# KeyCade.net
KiCad netlist of a schematic drawn in EAGLE
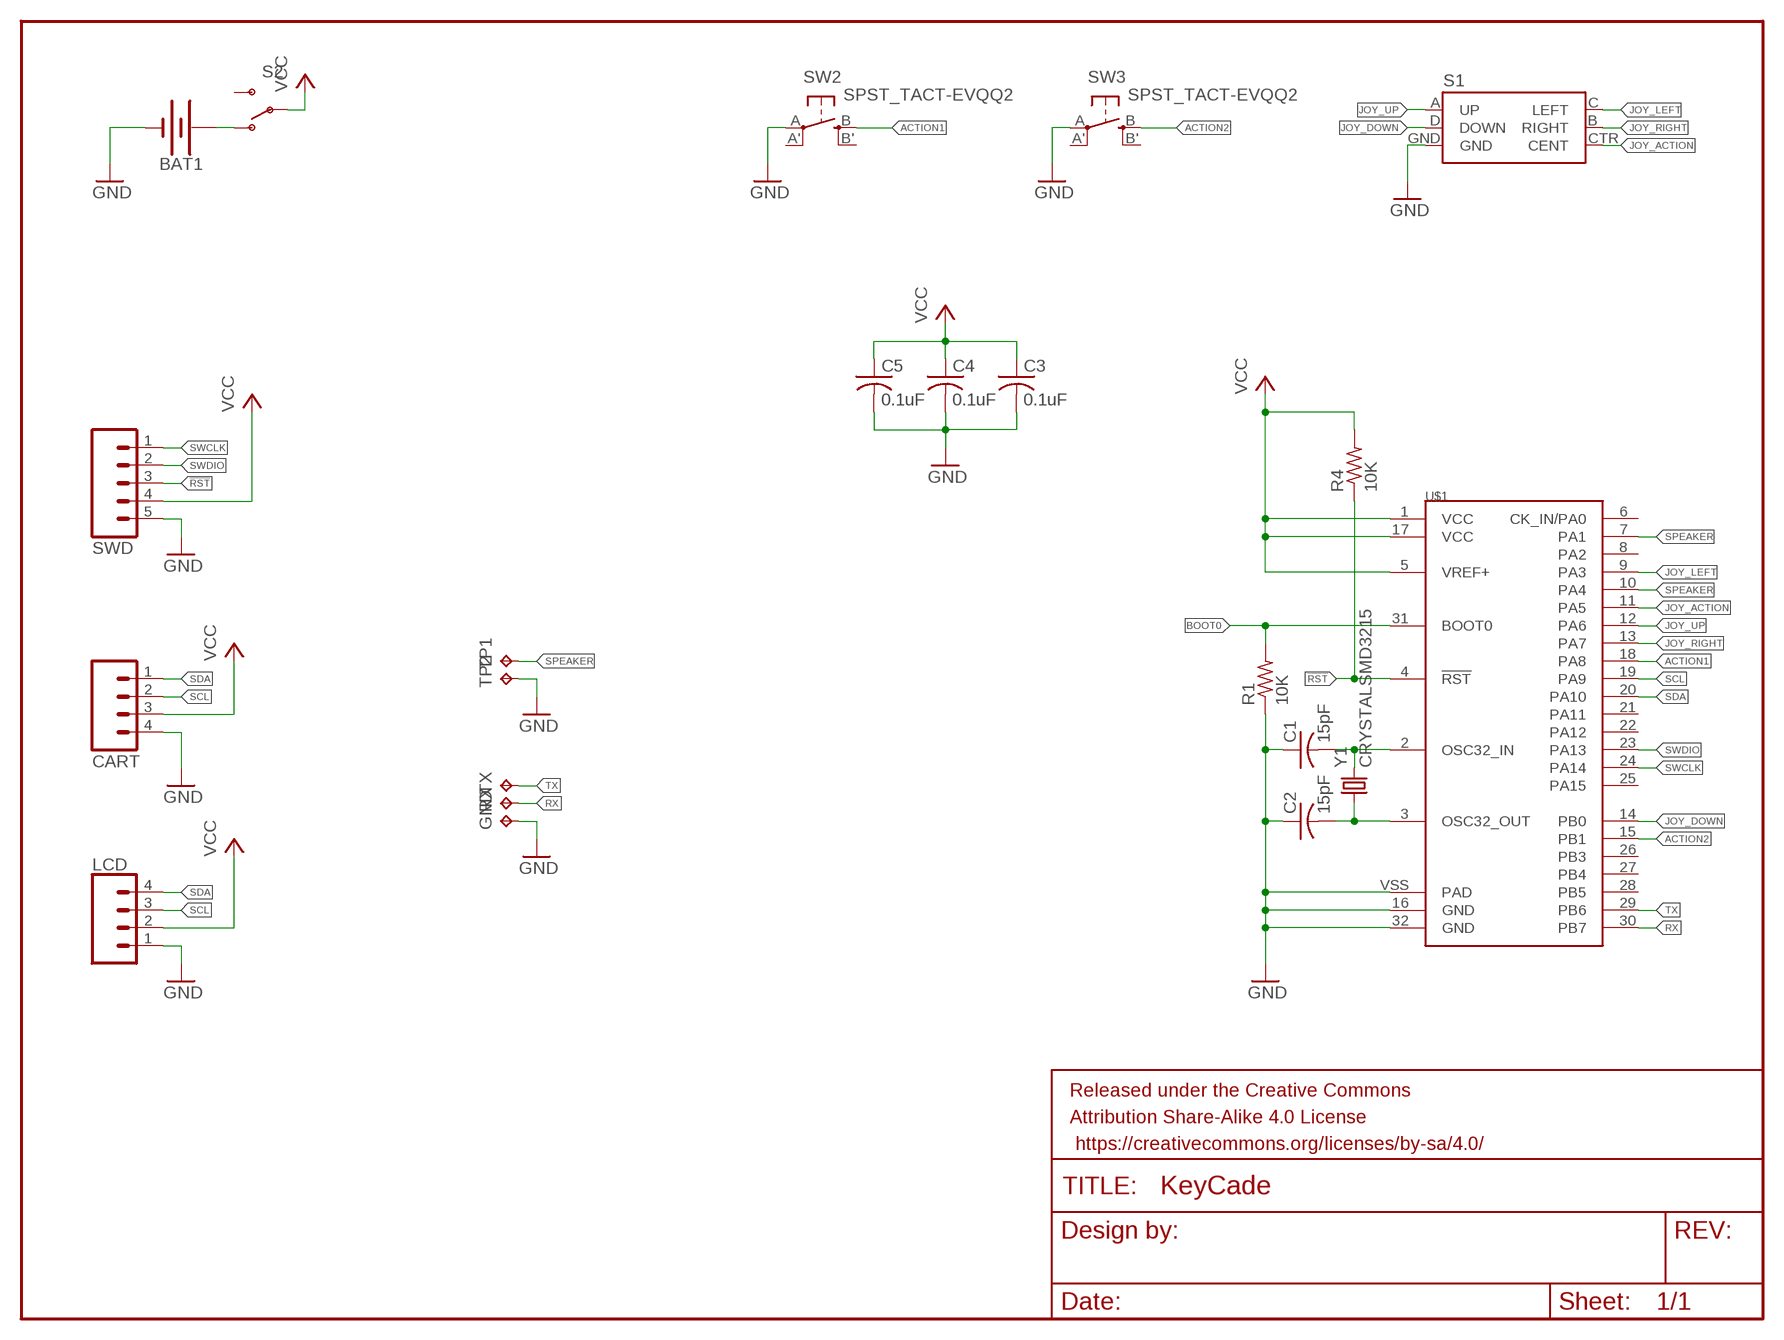
[diagram p0: schematic, sheet 1]

(export (version "E")
  (design (tool "Eeschema 10.0.6"))
  (components
    (comp (ref "BAT1")
      (value "BATTERY-20MM_SMD_4LEGS")
      (footprint "eagle-import:BATTCON_20MM_4LEGS")
      (libsource (lib "eagle-import") (part "BATTERY-20MM_SMD_4LEGS"))
    )
    (comp (ref "C1")
      (value "15pF")
      (footprint "eagle-import:C0603")
      (libsource (lib "eagle-import") (part "C-USC0603"))
    )
    (comp (ref "C2")
      (value "15pF")
      (footprint "eagle-import:C0603")
      (libsource (lib "eagle-import") (part "C-USC0603"))
    )
    (comp (ref "C3")
      (value "0.1uF")
      (footprint "eagle-import:C0603")
      (libsource (lib "eagle-import") (part "C-USC0603"))
    )
    (comp (ref "C4")
      (value "0.1uF")
      (footprint "eagle-import:C0603")
      (libsource (lib "eagle-import") (part "C-USC0603"))
    )
    (comp (ref "C5")
      (value "0.1uF")
      (footprint "eagle-import:C0603")
      (libsource (lib "eagle-import") (part "C-USC0603"))
    )
    (comp (ref "CART")
      (value "M04PTH")
      (footprint "eagle-import:1X04@1")
      (libsource (lib "eagle-import") (part "M04PTH"))
    )
    (comp (ref "FRAME1")
      (value "FRAME-LETTER")
      (footprint "eagle-import:CREATIVE_COMMONS")
      (libsource (lib "eagle-import") (part "FRAME-LETTER"))
    )
    (comp (ref "GND")
      (value "TPTP17SQ")
      (footprint "eagle-import:TP17SQ")
      (libsource (lib "eagle-import") (part "TPTP17SQ"))
    )
    (comp (ref "LCD")
      (value "CONN_04SMD_RA_FEMALE")
      (footprint "eagle-import:1X04_SMD_RA_FEMALE")
      (libsource (lib "eagle-import") (part "CONN_04SMD_RA_FEMALE"))
    )
    (comp (ref "R1")
      (value "10K")
      (footprint "eagle-import:R0603")
      (libsource (lib "eagle-import") (part "R-US_R0603"))
    )
    (comp (ref "R4")
      (value "10K")
      (footprint "eagle-import:R0603")
      (libsource (lib "eagle-import") (part "R-US_R0603"))
    )
    (comp (ref "RX")
      (value "TPTP17SQ")
      (footprint "eagle-import:TP17SQ")
      (libsource (lib "eagle-import") (part "TPTP17SQ"))
    )
    (comp (ref "S1")
      (value "JOYSTICK_MINI")
      (footprint "eagle-import:JOYSTICK_MINI")
      (libsource (lib "eagle-import") (part "JOYSTICK_MINI"))
    )
    (comp (ref "S2")
      (value "SWITCH-SPDT-SMD-A")
      (footprint "eagle-import:SWITCH-SPST-SMD-A")
      (libsource (lib "eagle-import") (part "SWITCH-SPDT-SMD-A"))
    )
    (comp (ref "SW2")
      (value "SPST_TACT-EVQQ2")
      (footprint "eagle-import:EVQ-Q2")
      (libsource (lib "eagle-import") (part "SPST_TACT-EVQQ2"))
    )
    (comp (ref "SW3")
      (value "SPST_TACT-EVQQ2")
      (footprint "eagle-import:EVQ-Q2")
      (libsource (lib "eagle-import") (part "SPST_TACT-EVQQ2"))
    )
    (comp (ref "SWD")
      (value "M05PTH")
      (footprint "eagle-import:1X05")
      (libsource (lib "eagle-import") (part "M05PTH"))
    )
    (comp (ref "TP1")
      (value "TPTP17SQ")
      (footprint "eagle-import:TP17SQ")
      (libsource (lib "eagle-import") (part "TPTP17SQ"))
    )
    (comp (ref "TP2")
      (value "TPTP17SQ")
      (footprint "eagle-import:TP17SQ")
      (libsource (lib "eagle-import") (part "TPTP17SQ"))
    )
    (comp (ref "TX")
      (value "TPTP17SQ")
      (footprint "eagle-import:TP17SQ")
      (libsource (lib "eagle-import") (part "TPTP17SQ"))
    )
    (comp (ref "U$1")
      (value "STM32L432KCIC")
      (footprint "eagle-import:UFQFPN32")
      (libsource (lib "eagle-import") (part "STM32L432KCIC"))
    )
    (comp (ref "Y1")
      (value "CRYSTALSMD3215")
      (footprint "eagle-import:ST3215SB_32X15")
      (libsource (lib "eagle-import") (part "CRYSTALSMD3215"))
    )
  )
  (nets
    (net (code "1") (name "/~{RST}") (class "Default")
      (node (ref "R4") (pin "1") (pinfunction "1_1") (pintype "passive"))
      (node (ref "SWD") (pin "3") (pinfunction "3_3") (pintype "passive"))
      (node (ref "U$1") (pin "4") (pinfunction "~{RST}_4") (pintype "bidirectional"))
    )
    (net (code "2") (name "ACTION1") (class "Default")
      (node (ref "SW2") (pin "B") (pinfunction "S_B") (pintype "passive"))
      (node (ref "U$1") (pin "18") (pinfunction "PA8_18") (pintype "bidirectional"))
    )
    (net (code "3") (name "ACTION2") (class "Default")
      (node (ref "SW3") (pin "B") (pinfunction "S_B") (pintype "passive"))
      (node (ref "U$1") (pin "15") (pinfunction "PB1_15") (pintype "bidirectional"))
    )
    (net (code "4") (name "BOOT0") (class "Default")
      (node (ref "R1") (pin "2") (pinfunction "2_2") (pintype "passive"))
      (node (ref "U$1") (pin "31") (pinfunction "BOOT0_31") (pintype "bidirectional"))
    )
    (net (code "5") (name "GND") (class "Default")
      (node (ref "BAT1") (pin "NEGATIVE") (pinfunction "-_NEGATIVE") (pintype "power_in"))
      (node (ref "C1") (pin "1") (pinfunction "1_1") (pintype "passive"))
      (node (ref "C2") (pin "1") (pinfunction "1_1") (pintype "passive"))
      (node (ref "C3") (pin "2") (pinfunction "2_2") (pintype "passive"))
      (node (ref "C4") (pin "2") (pinfunction "2_2") (pintype "passive"))
      (node (ref "C5") (pin "2") (pinfunction "2_2") (pintype "passive"))
      (node (ref "CART") (pin "4") (pinfunction "4_4") (pintype "passive"))
      (node (ref "GND") (pin "TP") (pinfunction "TP_TP") (pintype "input"))
      (node (ref "LCD") (pin "1") (pinfunction "1_1") (pintype "passive"))
      (node (ref "R1") (pin "1") (pinfunction "1_1") (pintype "passive"))
      (node (ref "S1") (pin "GND") (pinfunction "GND_GND") (pintype "bidirectional"))
      (node (ref "SW2") (pin "A") (pinfunction "P_A") (pintype "passive"))
      (node (ref "SW3") (pin "A") (pinfunction "P_A") (pintype "passive"))
      (node (ref "SWD") (pin "5") (pinfunction "5_5") (pintype "passive"))
      (node (ref "TP2") (pin "TP") (pinfunction "TP_TP") (pintype "input"))
      (node (ref "U$1") (pin "16") (pinfunction "GND_16") (pintype "bidirectional"))
      (node (ref "U$1") (pin "32") (pinfunction "GND_32") (pintype "bidirectional"))
      (node (ref "U$1") (pin "VSS") (pinfunction "PAD_VSS") (pintype "bidirectional"))
    )
    (net (code "6") (name "JOY_ACTION") (class "Default")
      (node (ref "S1") (pin "CTR") (pinfunction "CENT_CTR") (pintype "bidirectional"))
      (node (ref "U$1") (pin "11") (pinfunction "PA5_11") (pintype "bidirectional"))
    )
    (net (code "7") (name "JOY_DOWN") (class "Default")
      (node (ref "S1") (pin "D") (pinfunction "DOWN_D") (pintype "bidirectional"))
      (node (ref "U$1") (pin "14") (pinfunction "PB0_14") (pintype "bidirectional"))
    )
    (net (code "8") (name "JOY_LEFT") (class "Default")
      (node (ref "S1") (pin "C") (pinfunction "LEFT_C") (pintype "bidirectional"))
      (node (ref "U$1") (pin "9") (pinfunction "PA3_9") (pintype "bidirectional"))
    )
    (net (code "9") (name "JOY_RIGHT") (class "Default")
      (node (ref "S1") (pin "B") (pinfunction "RIGHT_B") (pintype "bidirectional"))
      (node (ref "U$1") (pin "13") (pinfunction "PA7_13") (pintype "bidirectional"))
    )
    (net (code "10") (name "JOY_UP") (class "Default")
      (node (ref "S1") (pin "A") (pinfunction "UP_A") (pintype "bidirectional"))
      (node (ref "U$1") (pin "12") (pinfunction "PA6_12") (pintype "bidirectional"))
    )
    (net (code "11") (name "Net-(S2-O)") (class "Default")
      (node (ref "BAT1") (pin "POSITIVE@1") (pinfunction "+_POSITIVE@1") (pintype "power_in"))
      (node (ref "BAT1") (pin "POSITIVE@2") (pinfunction "+_POSITIVE@2") (pintype "power_in"))
      (node (ref "BAT1") (pin "POSITIVE@3") (pinfunction "+_POSITIVE@3") (pintype "power_in"))
      (node (ref "BAT1") (pin "POSITIVE@4") (pinfunction "+_POSITIVE@4") (pintype "power_in"))
      (node (ref "S2") (pin "1") (pinfunction "O_1") (pintype "passive"))
    )
    (net (code "12") (name "Net-(U$1-OSC32_IN)") (class "Default")
      (node (ref "C1") (pin "2") (pinfunction "2_2") (pintype "passive"))
      (node (ref "U$1") (pin "2") (pinfunction "OSC32_IN_2") (pintype "bidirectional"))
      (node (ref "Y1") (pin "2") (pinfunction "2_2") (pintype "passive"))
    )
    (net (code "13") (name "Net-(U$1-OSC32_OUT)") (class "Default")
      (node (ref "C2") (pin "2") (pinfunction "2_2") (pintype "passive"))
      (node (ref "U$1") (pin "3") (pinfunction "OSC32_OUT_3") (pintype "bidirectional"))
      (node (ref "Y1") (pin "1") (pinfunction "1_1") (pintype "passive"))
    )
    (net (code "14") (name "RX") (class "Default")
      (node (ref "RX") (pin "TP") (pinfunction "TP_TP") (pintype "input"))
      (node (ref "U$1") (pin "30") (pinfunction "PB7_30") (pintype "bidirectional"))
    )
    (net (code "15") (name "SCL") (class "Default")
      (node (ref "CART") (pin "2") (pinfunction "2_2") (pintype "passive"))
      (node (ref "LCD") (pin "3") (pinfunction "3_3") (pintype "passive"))
      (node (ref "U$1") (pin "19") (pinfunction "PA9_19") (pintype "bidirectional"))
    )
    (net (code "16") (name "SDA") (class "Default")
      (node (ref "CART") (pin "1") (pinfunction "1_1") (pintype "passive"))
      (node (ref "LCD") (pin "4") (pinfunction "4_4") (pintype "passive"))
      (node (ref "U$1") (pin "20") (pinfunction "PA10_20") (pintype "bidirectional"))
    )
    (net (code "17") (name "SPEAKER") (class "Default")
      (node (ref "TP1") (pin "TP") (pinfunction "TP_TP") (pintype "input"))
      (node (ref "U$1") (pin "10") (pinfunction "PA4_10") (pintype "bidirectional"))
      (node (ref "U$1") (pin "7") (pinfunction "PA1_7") (pintype "bidirectional"))
    )
    (net (code "18") (name "SWCLK") (class "Default")
      (node (ref "SWD") (pin "1") (pinfunction "1_1") (pintype "passive"))
      (node (ref "U$1") (pin "24") (pinfunction "PA14_24") (pintype "bidirectional"))
    )
    (net (code "19") (name "SWDIO") (class "Default")
      (node (ref "SWD") (pin "2") (pinfunction "2_2") (pintype "passive"))
      (node (ref "U$1") (pin "23") (pinfunction "PA13_23") (pintype "bidirectional"))
    )
    (net (code "20") (name "TX") (class "Default")
      (node (ref "TX") (pin "TP") (pinfunction "TP_TP") (pintype "input"))
      (node (ref "U$1") (pin "29") (pinfunction "PB6_29") (pintype "bidirectional"))
    )
    (net (code "21") (name "VCC") (class "Default")
      (node (ref "C3") (pin "1") (pinfunction "1_1") (pintype "passive"))
      (node (ref "C4") (pin "1") (pinfunction "1_1") (pintype "passive"))
      (node (ref "C5") (pin "1") (pinfunction "1_1") (pintype "passive"))
      (node (ref "CART") (pin "3") (pinfunction "3_3") (pintype "passive"))
      (node (ref "LCD") (pin "2") (pinfunction "2_2") (pintype "passive"))
      (node (ref "R4") (pin "2") (pinfunction "2_2") (pintype "passive"))
      (node (ref "S2") (pin "2") (pinfunction "P_2") (pintype "passive"))
      (node (ref "SWD") (pin "4") (pinfunction "4_4") (pintype "passive"))
      (node (ref "U$1") (pin "1") (pinfunction "VCC_1") (pintype "bidirectional"))
      (node (ref "U$1") (pin "17") (pinfunction "VCC_17") (pintype "bidirectional"))
      (node (ref "U$1") (pin "5") (pinfunction "VREF+_5") (pintype "bidirectional"))
    )
    (net (code "22") (name "unconnected-(S2-S-Pad3)") (class "Default")
      (node (ref "S2") (pin "3") (pinfunction "S_3") (pintype "passive"))
    )
    (net (code "23") (name "unconnected-(SW2-P1-PadA')") (class "Default")
      (node (ref "SW2") (pin "A'") (pinfunction "P1_A'") (pintype "passive"))
    )
    (net (code "24") (name "unconnected-(SW2-S1-PadB')") (class "Default")
      (node (ref "SW2") (pin "B'") (pinfunction "S1_B'") (pintype "passive"))
    )
    (net (code "25") (name "unconnected-(SW3-P1-PadA')") (class "Default")
      (node (ref "SW3") (pin "A'") (pinfunction "P1_A'") (pintype "passive"))
    )
    (net (code "26") (name "unconnected-(SW3-S1-PadB')") (class "Default")
      (node (ref "SW3") (pin "B'") (pinfunction "S1_B'") (pintype "passive"))
    )
    (net (code "27") (name "unconnected-(U$1-CK_IN{slash}PA0-Pad6)") (class "Default")
      (node (ref "U$1") (pin "6") (pinfunction "CK_IN/PA0_6") (pintype "bidirectional"))
    )
    (net (code "28") (name "unconnected-(U$1-PA2-Pad8)") (class "Default")
      (node (ref "U$1") (pin "8") (pinfunction "PA2_8") (pintype "bidirectional"))
    )
    (net (code "29") (name "unconnected-(U$1-PA11-Pad21)") (class "Default")
      (node (ref "U$1") (pin "21") (pinfunction "PA11_21") (pintype "bidirectional"))
    )
    (net (code "30") (name "unconnected-(U$1-PA12-Pad22)") (class "Default")
      (node (ref "U$1") (pin "22") (pinfunction "PA12_22") (pintype "bidirectional"))
    )
    (net (code "31") (name "unconnected-(U$1-PA15-Pad25)") (class "Default")
      (node (ref "U$1") (pin "25") (pinfunction "PA15_25") (pintype "bidirectional"))
    )
    (net (code "32") (name "unconnected-(U$1-PB3-Pad26)") (class "Default")
      (node (ref "U$1") (pin "26") (pinfunction "PB3_26") (pintype "bidirectional"))
    )
    (net (code "33") (name "unconnected-(U$1-PB4-Pad27)") (class "Default")
      (node (ref "U$1") (pin "27") (pinfunction "PB4_27") (pintype "bidirectional"))
    )
    (net (code "34") (name "unconnected-(U$1-PB5-Pad28)") (class "Default")
      (node (ref "U$1") (pin "28") (pinfunction "PB5_28") (pintype "bidirectional"))
    )
  )
)
